# Schematic_Kelompok12.net
KiCad netlist of a schematic drawn in EAGLE
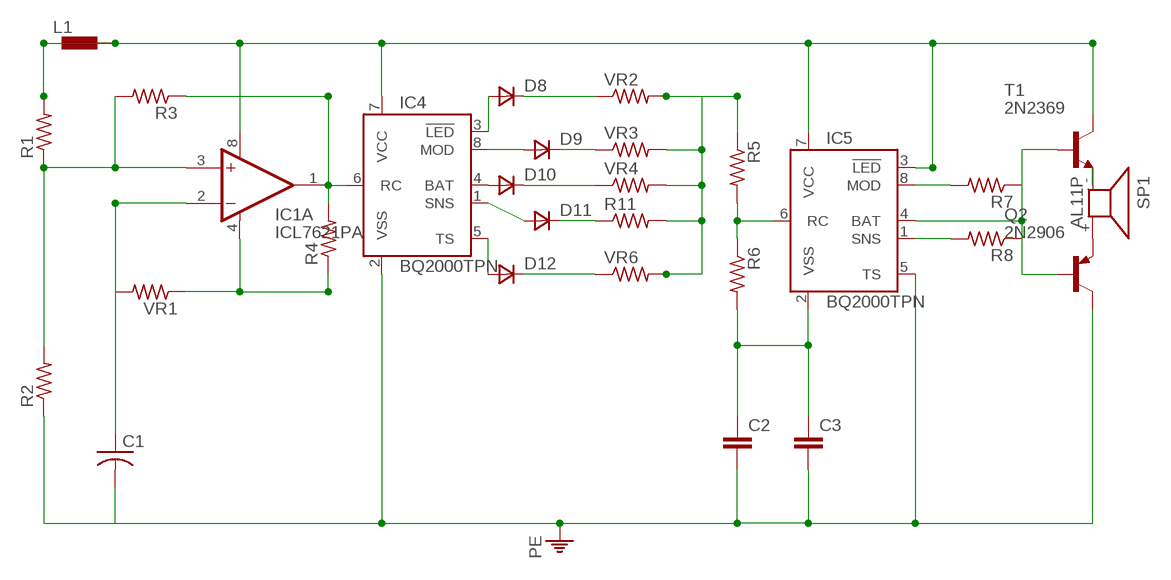
[diagram p0: schematic, sheet 1]

(export (version "E")
  (design (tool "Eeschema 10.0.6"))
  (components
    (comp (ref "C1")
      (value "C-US025-030X050")
      (footprint "eagle-import:C025-030X050")
      (libsource (lib "eagle-import") (part "C-US025-030X050"))
    )
    (comp (ref "C2")
      (value "C-EU025-030X050")
      (footprint "eagle-import:C025-030X050")
      (libsource (lib "eagle-import") (part "C-EU025-030X050"))
    )
    (comp (ref "C3")
      (value "C-EU025-030X050")
      (footprint "eagle-import:C025-030X050")
      (libsource (lib "eagle-import") (part "C-EU025-030X050"))
    )
    (comp (ref "D8")
      (value "D_E2L")
      (footprint "eagle-import:E2LINE")
      (libsource (lib "eagle-import") (part "D_E2L"))
    )
    (comp (ref "D9")
      (value "D_E2L")
      (footprint "eagle-import:E2LINE")
      (libsource (lib "eagle-import") (part "D_E2L"))
    )
    (comp (ref "D10")
      (value "D_E2L")
      (footprint "eagle-import:E2LINE")
      (libsource (lib "eagle-import") (part "D_E2L"))
    )
    (comp (ref "D11")
      (value "D_E2L")
      (footprint "eagle-import:E2LINE")
      (libsource (lib "eagle-import") (part "D_E2L"))
    )
    (comp (ref "D12")
      (value "D_E2L")
      (footprint "eagle-import:E2LINE")
      (libsource (lib "eagle-import") (part "D_E2L"))
    )
    (comp (ref "IC1")
      (value "ICL7621PA")
      (footprint "eagle-import:DIL08")
      (libsource (lib "eagle-import") (part "ICL7621PA"))
    )
    (comp (ref "IC4")
      (value "BQ2000TPN")
      (footprint "eagle-import:DIL08")
      (fields (field (name "MF") "TEXAS INSTRUMENT CONNECTORS") (field (name "MPN") "BQ2000TPN-B5"))
      (libsource (lib "eagle-import") (part "BQ2000TPN"))
    )
    (comp (ref "IC5")
      (value "BQ2000TPN")
      (footprint "eagle-import:DIL08")
      (fields (field (name "MF") "TEXAS INSTRUMENT CONNECTORS") (field (name "MPN") "BQ2000TPN-B5"))
      (libsource (lib "eagle-import") (part "BQ2000TPN"))
    )
    (comp (ref "L1")
      (value "DR1030")
      (footprint "eagle-import:DR1030")
      (libsource (lib "eagle-import") (part "DR1030"))
    )
    (comp (ref "Q2")
      (value "2N2906")
      (footprint "eagle-import:TO18")
      (libsource (lib "eagle-import") (part "2N2906"))
    )
    (comp (ref "R1")
      (value "R-US_0204/7")
      (footprint "eagle-import:0204_7")
      (libsource (lib "eagle-import") (part "R-US_0204/7"))
    )
    (comp (ref "R2")
      (value "R-US_0309/12")
      (footprint "eagle-import:0309_12")
      (libsource (lib "eagle-import") (part "R-US_0309/12"))
    )
    (comp (ref "R3")
      (value "R-US_0309/12")
      (footprint "eagle-import:0309_12")
      (libsource (lib "eagle-import") (part "R-US_0309/12"))
    )
    (comp (ref "R4")
      (value "R-US_0309/12")
      (footprint "eagle-import:0309_12")
      (libsource (lib "eagle-import") (part "R-US_0309/12"))
    )
    (comp (ref "R5")
      (value "R-US_0309/12")
      (footprint "eagle-import:0309_12")
      (libsource (lib "eagle-import") (part "R-US_0309/12"))
    )
    (comp (ref "R6")
      (value "R-US_0309/12")
      (footprint "eagle-import:0309_12")
      (libsource (lib "eagle-import") (part "R-US_0309/12"))
    )
    (comp (ref "R7")
      (value "R-US_0309/12")
      (footprint "eagle-import:0309_12")
      (libsource (lib "eagle-import") (part "R-US_0309/12"))
    )
    (comp (ref "R8")
      (value "R-US_0309/12")
      (footprint "eagle-import:0309_12")
      (libsource (lib "eagle-import") (part "R-US_0309/12"))
    )
    (comp (ref "R11")
      (value "R-US_0204/7")
      (footprint "eagle-import:0204_7")
      (libsource (lib "eagle-import") (part "R-US_0204/7"))
    )
    (comp (ref "SP1")
      (value "AL11P")
      (footprint "eagle-import:AL11P")
      (libsource (lib "eagle-import") (part "AL11P"))
    )
    (comp (ref "T1")
      (value "2N2369")
      (footprint "eagle-import:TO18")
      (libsource (lib "eagle-import") (part "2N2369"))
    )
    (comp (ref "VR1")
      (value "R-US_0309/12")
      (footprint "eagle-import:0309_12")
      (libsource (lib "eagle-import") (part "R-US_0309/12"))
    )
    (comp (ref "VR2")
      (value "R-US_0204/7")
      (footprint "eagle-import:0204_7")
      (libsource (lib "eagle-import") (part "R-US_0204/7"))
    )
    (comp (ref "VR3")
      (value "R-US_0204/7")
      (footprint "eagle-import:0204_7")
      (libsource (lib "eagle-import") (part "R-US_0204/7"))
    )
    (comp (ref "VR4")
      (value "R-US_0204/7")
      (footprint "eagle-import:0204_7")
      (libsource (lib "eagle-import") (part "R-US_0204/7"))
    )
    (comp (ref "VR6")
      (value "R-US_0204/7")
      (footprint "eagle-import:0204_7")
      (libsource (lib "eagle-import") (part "R-US_0204/7"))
    )
  )
  (nets
    (net (code "1") (name "Net-(D8-A)") (class "Default")
      (node (ref "D8") (pin "2") (pinfunction "A_2") (pintype "passive"))
      (node (ref "IC4") (pin "3") (pinfunction "~{LED}_3") (pintype "output"))
    )
    (net (code "2") (name "Net-(D8-C)") (class "Default")
      (node (ref "D8") (pin "1") (pinfunction "C_1") (pintype "passive"))
      (node (ref "VR2") (pin "1") (pinfunction "1_1") (pintype "passive"))
    )
    (net (code "3") (name "Net-(D9-A)") (class "Default")
      (node (ref "D9") (pin "2") (pinfunction "A_2") (pintype "passive"))
      (node (ref "IC4") (pin "8") (pinfunction "MOD_8") (pintype "output"))
    )
    (net (code "4") (name "Net-(D9-C)") (class "Default")
      (node (ref "D9") (pin "1") (pinfunction "C_1") (pintype "passive"))
      (node (ref "VR3") (pin "1") (pinfunction "1_1") (pintype "passive"))
    )
    (net (code "5") (name "Net-(D10-A)") (class "Default")
      (node (ref "D10") (pin "2") (pinfunction "A_2") (pintype "passive"))
      (node (ref "IC4") (pin "4") (pinfunction "BAT_4") (pintype "input"))
    )
    (net (code "6") (name "Net-(D10-C)") (class "Default")
      (node (ref "D10") (pin "1") (pinfunction "C_1") (pintype "passive"))
      (node (ref "VR4") (pin "1") (pinfunction "1_1") (pintype "passive"))
    )
    (net (code "7") (name "Net-(D11-A)") (class "Default")
      (node (ref "D11") (pin "2") (pinfunction "A_2") (pintype "passive"))
      (node (ref "IC4") (pin "1") (pinfunction "SNS_1") (pintype "input"))
    )
    (net (code "8") (name "Net-(D11-C)") (class "Default")
      (node (ref "D11") (pin "1") (pinfunction "C_1") (pintype "passive"))
      (node (ref "R11") (pin "1") (pinfunction "1_1") (pintype "passive"))
    )
    (net (code "9") (name "Net-(D12-A)") (class "Default")
      (node (ref "D12") (pin "2") (pinfunction "A_2") (pintype "passive"))
      (node (ref "IC4") (pin "5") (pinfunction "TS_5") (pintype "input"))
    )
    (net (code "10") (name "Net-(D12-C)") (class "Default")
      (node (ref "D12") (pin "1") (pinfunction "C_1") (pintype "passive"))
      (node (ref "VR6") (pin "1") (pinfunction "1_1") (pintype "passive"))
    )
    (net (code "11") (name "Net-(IC1A-+IN)") (class "Default")
      (node (ref "IC1") (pin "3") (pinfunction "+IN_3") (pintype "input"))
      (node (ref "R1") (pin "1") (pinfunction "1_1") (pintype "passive"))
      (node (ref "R2") (pin "2") (pinfunction "2_2") (pintype "passive"))
      (node (ref "R3") (pin "2") (pinfunction "2_2") (pintype "passive"))
    )
    (net (code "12") (name "Net-(IC1A--IN)") (class "Default")
      (node (ref "C1") (pin "1") (pinfunction "1_1") (pintype "passive"))
      (node (ref "IC1") (pin "2") (pinfunction "-IN_2") (pintype "input"))
      (node (ref "VR1") (pin "2") (pinfunction "2_2") (pintype "passive"))
    )
    (net (code "13") (name "Net-(IC1A-OUT)") (class "Default")
      (node (ref "IC1") (pin "1") (pinfunction "OUT_1") (pintype "output"))
      (node (ref "IC4") (pin "6") (pinfunction "RC_6") (pintype "input"))
      (node (ref "R3") (pin "1") (pinfunction "1_1") (pintype "passive"))
      (node (ref "R4") (pin "2") (pinfunction "2_2") (pintype "passive"))
    )
    (net (code "14") (name "Net-(IC1A-V+)") (class "Default")
      (node (ref "IC1") (pin "8") (pinfunction "V+_8") (pintype "power_in"))
      (node (ref "IC4") (pin "7") (pinfunction "VCC_7") (pintype "input"))
      (node (ref "IC5") (pin "3") (pinfunction "~{LED}_3") (pintype "output"))
      (node (ref "IC5") (pin "7") (pinfunction "VCC_7") (pintype "input"))
      (node (ref "L1") (pin "1") (pinfunction "1_1") (pintype "passive"))
      (node (ref "L1") (pin "2") (pinfunction "2_2") (pintype "passive"))
      (node (ref "R1") (pin "2") (pinfunction "2_2") (pintype "passive"))
      (node (ref "T1") (pin "3") (pinfunction "C_3") (pintype "passive"))
    )
    (net (code "15") (name "Net-(IC1A-V-)") (class "Default")
      (node (ref "IC1") (pin "4") (pinfunction "V-_4") (pintype "power_in"))
      (node (ref "R4") (pin "1") (pinfunction "1_1") (pintype "passive"))
      (node (ref "VR1") (pin "1") (pinfunction "1_1") (pintype "passive"))
    )
    (net (code "16") (name "Net-(IC5-BAT)") (class "Default")
      (node (ref "IC5") (pin "4") (pinfunction "BAT_4") (pintype "input"))
      (node (ref "Q2") (pin "2") (pinfunction "B_2") (pintype "passive"))
      (node (ref "R7") (pin "1") (pinfunction "1_1") (pintype "passive"))
      (node (ref "R8") (pin "1") (pinfunction "1_1") (pintype "passive"))
      (node (ref "T1") (pin "2") (pinfunction "B_2") (pintype "passive"))
    )
    (net (code "17") (name "Net-(IC5-MOD)") (class "Default")
      (node (ref "IC5") (pin "8") (pinfunction "MOD_8") (pintype "output"))
      (node (ref "R7") (pin "2") (pinfunction "2_2") (pintype "passive"))
    )
    (net (code "18") (name "Net-(IC5-RC)") (class "Default")
      (node (ref "IC5") (pin "6") (pinfunction "RC_6") (pintype "input"))
      (node (ref "R5") (pin "2") (pinfunction "2_2") (pintype "passive"))
      (node (ref "R6") (pin "1") (pinfunction "1_1") (pintype "passive"))
    )
    (net (code "19") (name "Net-(IC5-SNS)") (class "Default")
      (node (ref "IC5") (pin "1") (pinfunction "SNS_1") (pintype "input"))
      (node (ref "R8") (pin "2") (pinfunction "2_2") (pintype "passive"))
    )
    (net (code "20") (name "Net-(IC5-VSS)") (class "Default")
      (node (ref "C2") (pin "1") (pinfunction "1_1") (pintype "passive"))
      (node (ref "C3") (pin "1") (pinfunction "1_1") (pintype "passive"))
      (node (ref "IC5") (pin "2") (pinfunction "VSS_2") (pintype "power_in"))
      (node (ref "R6") (pin "2") (pinfunction "2_2") (pintype "passive"))
    )
    (net (code "21") (name "Net-(Q2-E)") (class "Default")
      (node (ref "Q2") (pin "1") (pinfunction "E_1") (pintype "passive"))
      (node (ref "SP1") (pin "+") (pinfunction "2_+") (pintype "passive"))
    )
    (net (code "22") (name "Net-(R11-Pad2)") (class "Default")
      (node (ref "R11") (pin "2") (pinfunction "2_2") (pintype "passive"))
      (node (ref "R5") (pin "1") (pinfunction "1_1") (pintype "passive"))
      (node (ref "VR2") (pin "2") (pinfunction "2_2") (pintype "passive"))
      (node (ref "VR3") (pin "2") (pinfunction "2_2") (pintype "passive"))
      (node (ref "VR4") (pin "2") (pinfunction "2_2") (pintype "passive"))
      (node (ref "VR6") (pin "2") (pinfunction "2_2") (pintype "passive"))
    )
    (net (code "23") (name "Net-(SP1-1)") (class "Default")
      (node (ref "SP1") (pin "-") (pinfunction "1_-") (pintype "passive"))
      (node (ref "T1") (pin "1") (pinfunction "E_1") (pintype "passive"))
    )
    (net (code "24") (name "PE") (class "Default")
      (node (ref "C1") (pin "2") (pinfunction "2_2") (pintype "passive"))
      (node (ref "C2") (pin "2") (pinfunction "2_2") (pintype "passive"))
      (node (ref "C3") (pin "2") (pinfunction "2_2") (pintype "passive"))
      (node (ref "IC4") (pin "2") (pinfunction "VSS_2") (pintype "power_in"))
      (node (ref "IC5") (pin "5") (pinfunction "TS_5") (pintype "input"))
      (node (ref "Q2") (pin "3") (pinfunction "C_3") (pintype "passive"))
      (node (ref "R2") (pin "1") (pinfunction "1_1") (pintype "passive"))
    )
  )
)
